# Mikrolysreklamen15.net
KiCad netlist of a schematic drawn in Altium Designer
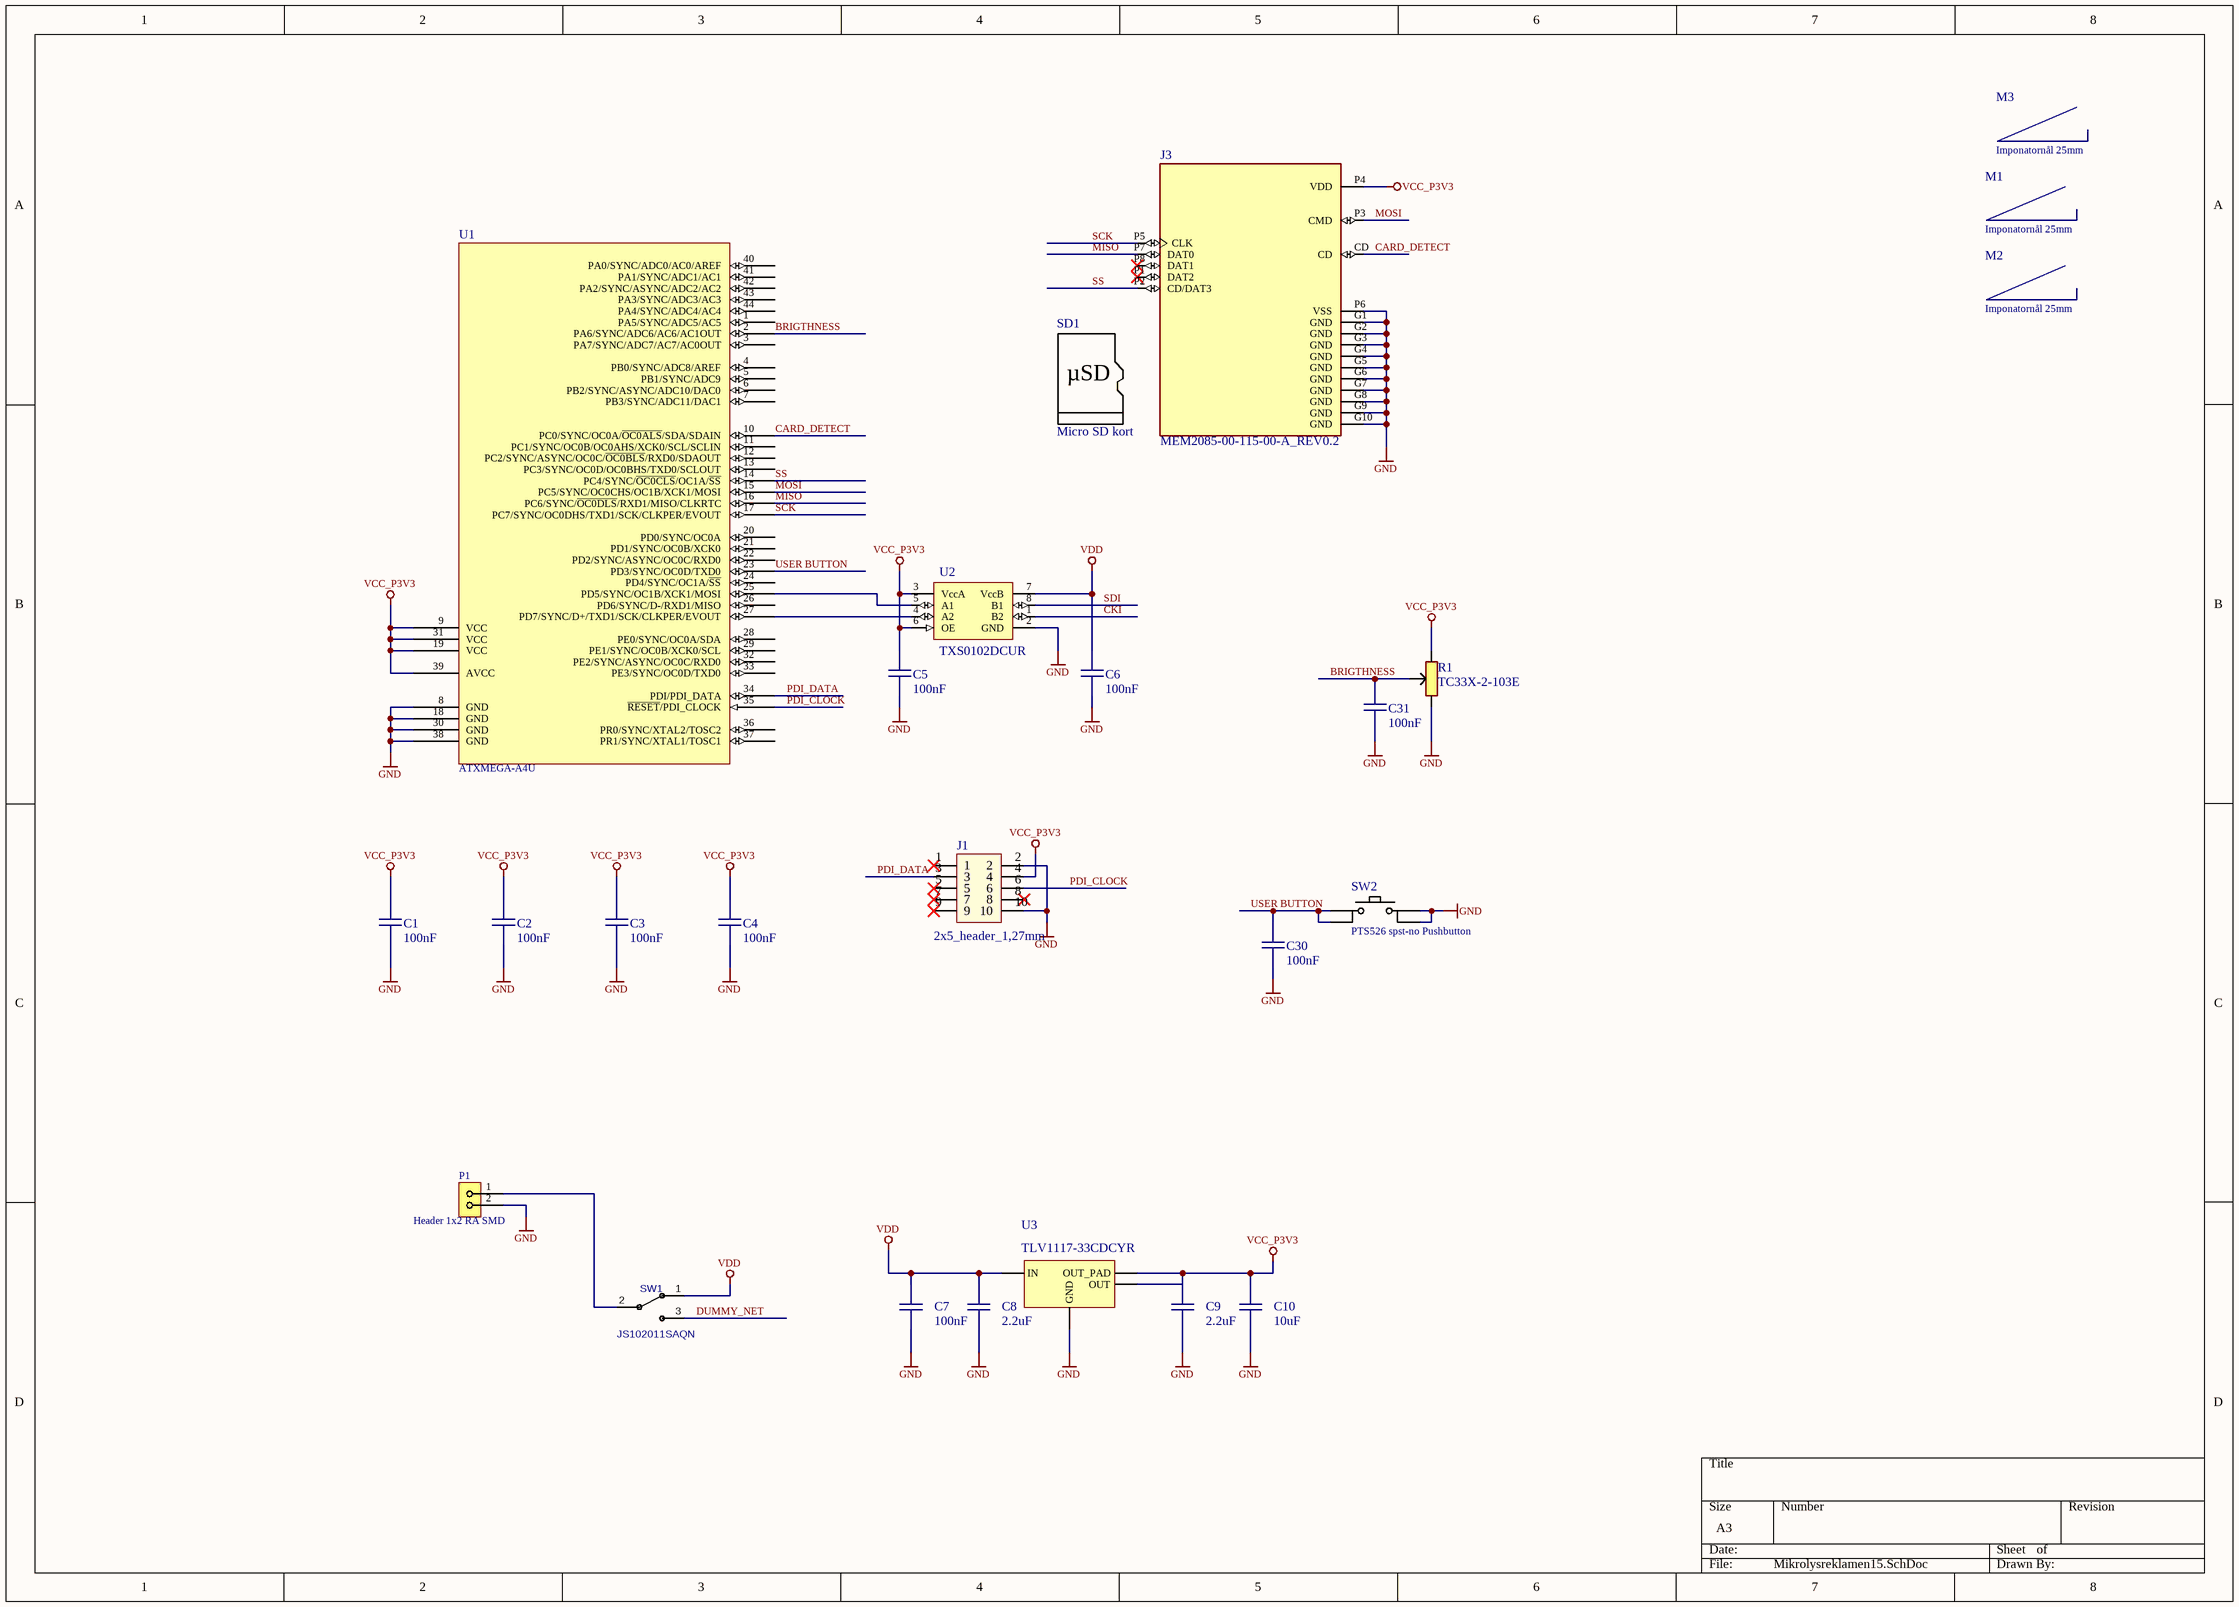
[diagram p0: Mikrolysreklamen15.SchDoc]

(export (version "E")
  (design (tool "Eeschema 10.0.6"))
  (components
    (comp (ref "C1")
      (value "100nF")
      (footprint "CAPC0603(1608)55_N")
      (libsource (lib "OVLib_64") (part "CAP"))
    )
    (comp (ref "C2")
      (value "100nF")
      (footprint "CAPC0603(1608)55_N")
      (libsource (lib "OVLib_64") (part "CAP"))
    )
    (comp (ref "C3")
      (value "100nF")
      (footprint "CAPC0603(1608)55_N")
      (libsource (lib "OVLib_64") (part "CAP"))
    )
    (comp (ref "C4")
      (value "100nF")
      (footprint "CAPC0603(1608)55_N")
      (libsource (lib "OVLib_64") (part "CAP"))
    )
    (comp (ref "C5")
      (value "100nF")
      (footprint "CAPC0603(1608)55_N")
      (libsource (lib "OVLib_64") (part "CAP"))
    )
    (comp (ref "C6")
      (value "100nF")
      (footprint "CAPC0603(1608)55_N")
      (libsource (lib "OVLib_64") (part "CAP"))
    )
    (comp (ref "C7")
      (value "100nF")
      (footprint "CAPC0603(1608)55_N")
      (libsource (lib "OVLib_64") (part "CAP"))
    )
    (comp (ref "C8")
      (value "2.2uF")
      (footprint "CAPC0603(1608)55_N")
      (libsource (lib "OVLib_64") (part "CAP"))
    )
    (comp (ref "C9")
      (value "2.2uF")
      (footprint "CAPC0603(1608)55_N")
      (libsource (lib "OVLib_64") (part "CAP"))
    )
    (comp (ref "C10")
      (value "10uF")
      (footprint "CAPC0805(2012)100_N")
      (libsource (lib "OVLib_64") (part "CAP"))
    )
    (comp (ref "C30")
      (value "100nF")
      (footprint "CAPC0603(1608)55_N")
      (libsource (lib "OVLib_64") (part "CAP"))
    )
    (comp (ref "C31")
      (value "100nF")
      (footprint "CAPC0603(1608)55_N")
      (libsource (lib "OVLib_64") (part "CAP"))
    )
    (comp (ref "J1")
      (value "2x5_header_1,27mm")
      (footprint "SMDHDRV10P127_2X5_615X330X560B")
      (libsource (lib "OVLib_64") (part "2x5_header_1,27mm"))
    )
    (comp (ref "J3")
      (value "MEM2085-00-115-00-A_REV0.2")
      (footprint "GCT_MEM2085-00-115-00-A_REV0.2")
      (description "MicroSD Push pull Memory Card Connector")
      (fields (field (name "MP") "MEM2085-00-115-00-A") (field (name "MF") "Global Connector Technology"))
      (libsource (lib "OVLib_64") (part "MEM2085-00-115-00-A_REV0.2"))
    )
    (comp (ref "M1")
      (value "Imponatornål 25mm")
      (footprint "Imponatornaal_liten")
      (description "nål til imponatorplate 25mm (Brooch back)")
      (libsource (lib "OVLib_64") (part "Imponatornaal"))
    )
    (comp (ref "M2")
      (value "Imponatornål 25mm")
      (footprint "Imponatornaal_liten")
      (description "nål til imponatorplate 25mm (Brooch back)")
      (libsource (lib "OVLib_64") (part "Imponatornaal"))
    )
    (comp (ref "M3")
      (value "Imponatornål 25mm")
      (footprint "Imponatornaal_liten")
      (description "nål til imponatorplate 25mm (Brooch back)")
      (libsource (lib "OVLib_64") (part "Imponatornaal"))
    )
    (comp (ref "P1") (value "Header 1x2 RA SMD") (libsource (lib "OVLib_64") (part "Header1x2")))
    (comp (ref "R1")
      (value "TC33X-2-103E")
      (footprint "TRIM_TC33X-2-103E")
      (libsource (lib "OVLib_64") (part "Potmeter"))
    )
    (comp (ref "SD1")
      (value "Micro SD kort")
      (footprint "microsdcard")
      (libsource (lib "OVLib_64") (part "microsdcard"))
    )
    (comp (ref "SW1") (value "JS102011SAQN") (libsource (lib "OVLib_64") (part "ToggleSwitch")))
    (comp (ref "SW2")
      (value "PTS526 spst-no Pushbutton")
      (footprint "PTS526_SK15_SMTR2_LFS")
      (libsource (lib "OVLib_64") (part "Pushbutton"))
    )
    (comp (ref "U1")
      (value "ATXMEGA-A4U")
      (footprint "TQFP80P1200X1200X120-44N")
      (libsource (lib "OVLib_64") (part "ATXMEGA-A4U"))
    )
    (comp (ref "U2") (value "TXS0102DCUR") (libsource (lib "OVLib_64") (part "TXS0102DCUR")))
    (comp (ref "U3")
      (value "TLV1117-33CDCYR")
      (footprint "SOT230P700X180-4N")
      (libsource (lib "OVLib_64") (part "LDO_REGULATOR"))
    )
  )
  (nets
    (net (code "1") (name "/BRIGTHNESS") (class "Default")
      (node (ref "C31") (pin "2") (pinfunction "2_2") (pintype "passive"))
      (node (ref "R1") (pin "2") (pinfunction "2_2") (pintype "passive"))
      (node (ref "U1") (pin "2") (pinfunction "PA6/SYNC/ADC6/AC6/AC1OUT_2") (pintype "bidirectional"))
    )
    (net (code "2") (name "/CARD_DETECT") (class "Default")
      (node (ref "J3") (pin "CD") (pinfunction "CD_CD") (pintype "bidirectional"))
      (node (ref "U1") (pin "10") (pinfunction "PC0/SYNC/OC0A/~{OC0ALS}/SDA/SDAIN_10") (pintype "bidirectional"))
    )
    (net (code "3") (name "/CKI") (class "Default")
      (node (ref "U2") (pin "1") (pinfunction "B2_1") (pintype "bidirectional"))
    )
    (net (code "4") (name "/DUMMY_NET") (class "Default")
      (node (ref "SW1") (pin "3") (pinfunction "3_3") (pintype "passive"))
    )
    (net (code "5") (name "/MISO") (class "Default")
      (node (ref "J3") (pin "P7") (pinfunction "DAT0_P7") (pintype "bidirectional"))
      (node (ref "U1") (pin "16") (pinfunction "PC6/SYNC/~{OC0DLS}/RXD1/MISO/CLKRTC_16") (pintype "bidirectional"))
    )
    (net (code "6") (name "/MOSI") (class "Default")
      (node (ref "J3") (pin "P3") (pinfunction "CMD_P3") (pintype "bidirectional"))
      (node (ref "U1") (pin "15") (pinfunction "PC5/SYNC/OC0CHS/OC1B/XCK1/MOSI_15") (pintype "bidirectional"))
    )
    (net (code "7") (name "/PDI_CLOCK") (class "Default")
      (node (ref "J1") (pin "6") (pinfunction "6_6") (pintype "power_in"))
      (node (ref "U1") (pin "35") (pinfunction "~{RESET}/PDI_CLOCK_35") (pintype "input"))
    )
    (net (code "8") (name "/PDI_DATA") (class "Default")
      (node (ref "J1") (pin "3") (pinfunction "3_3") (pintype "power_in"))
      (node (ref "U1") (pin "34") (pinfunction "PDI/PDI_DATA_34") (pintype "bidirectional"))
    )
    (net (code "9") (name "/SCK") (class "Default")
      (node (ref "J3") (pin "P5") (pinfunction "CLK_P5") (pintype "bidirectional"))
      (node (ref "U1") (pin "17") (pinfunction "PC7/SYNC/OC0DHS/TXD1/SCK/CLKPER/EVOUT_17") (pintype "bidirectional"))
    )
    (net (code "10") (name "/SDI") (class "Default")
      (node (ref "U2") (pin "8") (pinfunction "B1_8") (pintype "bidirectional"))
    )
    (net (code "11") (name "/SS") (class "Default")
      (node (ref "J3") (pin "P2") (pinfunction "CD/DAT3_P2") (pintype "bidirectional"))
      (node (ref "U1") (pin "14") (pinfunction "PC4/SYNC/~{OC0CLS}/OC1A/~{SS}_14") (pintype "bidirectional"))
    )
    (net (code "12") (name "/USER BUTTON") (class "Default")
      (node (ref "C30") (pin "2") (pinfunction "2_2") (pintype "passive"))
      (node (ref "SW2") (pin "1") (pinfunction "1_1") (pintype "passive"))
      (node (ref "SW2") (pin "2") (pinfunction "2_2") (pintype "passive"))
      (node (ref "U1") (pin "23") (pinfunction "PD3/SYNC/OC0D/TXD0_23") (pintype "bidirectional"))
    )
    (net (code "13") (name "GND") (class "Default")
      (node (ref "C1") (pin "1") (pinfunction "1_1") (pintype "passive"))
      (node (ref "C10") (pin "1") (pinfunction "1_1") (pintype "passive"))
      (node (ref "C2") (pin "1") (pinfunction "1_1") (pintype "passive"))
      (node (ref "C3") (pin "1") (pinfunction "1_1") (pintype "passive"))
      (node (ref "C30") (pin "1") (pinfunction "1_1") (pintype "passive"))
      (node (ref "C31") (pin "1") (pinfunction "1_1") (pintype "passive"))
      (node (ref "C4") (pin "1") (pinfunction "1_1") (pintype "passive"))
      (node (ref "C5") (pin "1") (pinfunction "1_1") (pintype "passive"))
      (node (ref "C6") (pin "1") (pinfunction "1_1") (pintype "passive"))
      (node (ref "C7") (pin "1") (pinfunction "1_1") (pintype "passive"))
      (node (ref "C8") (pin "1") (pinfunction "1_1") (pintype "passive"))
      (node (ref "C9") (pin "1") (pinfunction "1_1") (pintype "passive"))
      (node (ref "J1") (pin "10") (pinfunction "10_10") (pintype "power_in"))
      (node (ref "J1") (pin "2") (pinfunction "2_2") (pintype "power_in"))
      (node (ref "J3") (pin "G1") (pinfunction "GND_G1") (pintype "power_in"))
      (node (ref "J3") (pin "G10") (pinfunction "GND_G10") (pintype "power_in"))
      (node (ref "J3") (pin "G2") (pinfunction "GND_G2") (pintype "power_in"))
      (node (ref "J3") (pin "G3") (pinfunction "GND_G3") (pintype "power_in"))
      (node (ref "J3") (pin "G4") (pinfunction "GND_G4") (pintype "power_in"))
      (node (ref "J3") (pin "G5") (pinfunction "GND_G5") (pintype "power_in"))
      (node (ref "J3") (pin "G6") (pinfunction "GND_G6") (pintype "power_in"))
      (node (ref "J3") (pin "G7") (pinfunction "GND_G7") (pintype "power_in"))
      (node (ref "J3") (pin "G8") (pinfunction "GND_G8") (pintype "power_in"))
      (node (ref "J3") (pin "G9") (pinfunction "GND_G9") (pintype "power_in"))
      (node (ref "J3") (pin "P6") (pinfunction "VSS_P6") (pintype "power_in"))
      (node (ref "P1") (pin "2") (pinfunction "2_2") (pintype "passive"))
      (node (ref "R1") (pin "1") (pinfunction "1_1") (pintype "passive"))
      (node (ref "SW2") (pin "3") (pinfunction "3_3") (pintype "passive"))
      (node (ref "SW2") (pin "4") (pinfunction "4_4") (pintype "passive"))
      (node (ref "U1") (pin "18") (pinfunction "GND_18") (pintype "power_in"))
      (node (ref "U1") (pin "30") (pinfunction "GND_30") (pintype "power_in"))
      (node (ref "U1") (pin "38") (pinfunction "GND_38") (pintype "power_in"))
      (node (ref "U1") (pin "8") (pinfunction "GND_8") (pintype "power_in"))
      (node (ref "U2") (pin "2") (pinfunction "GND_2") (pintype "power_in"))
      (node (ref "U3") (pin "1") (pinfunction "GND_1") (pintype "power_in"))
    )
    (net (code "14") (name "Net-(P1-Pad1)") (class "Default")
      (node (ref "P1") (pin "1") (pinfunction "1_1") (pintype "passive"))
      (node (ref "SW1") (pin "2") (pinfunction "2_2") (pintype "passive"))
    )
    (net (code "15") (name "Net-(U1-PD5{slash}SYNC{slash}OC1B{slash}XCK1{slash}MOSI)") (class "Default")
      (node (ref "U1") (pin "25") (pinfunction "PD5/SYNC/OC1B/XCK1/MOSI_25") (pintype "bidirectional"))
      (node (ref "U2") (pin "5") (pinfunction "A1_5") (pintype "bidirectional"))
    )
    (net (code "16") (name "Net-(U1-PD7{slash}SYNC{slash}D+{slash}TXD1{slash}SCK{slash}CLKPER{slash}EVOUT)") (class "Default")
      (node (ref "U1") (pin "27") (pinfunction "PD7/SYNC/D+/TXD1/SCK/CLKPER/EVOUT_27") (pintype "bidirectional"))
      (node (ref "U2") (pin "4") (pinfunction "A2_4") (pintype "bidirectional"))
    )
    (net (code "17") (name "VCC_P3V3") (class "Default")
      (node (ref "C1") (pin "2") (pinfunction "2_2") (pintype "passive"))
      (node (ref "C10") (pin "2") (pinfunction "2_2") (pintype "passive"))
      (node (ref "C2") (pin "2") (pinfunction "2_2") (pintype "passive"))
      (node (ref "C3") (pin "2") (pinfunction "2_2") (pintype "passive"))
      (node (ref "C4") (pin "2") (pinfunction "2_2") (pintype "passive"))
      (node (ref "C5") (pin "2") (pinfunction "2_2") (pintype "passive"))
      (node (ref "C9") (pin "2") (pinfunction "2_2") (pintype "passive"))
      (node (ref "J1") (pin "4") (pinfunction "4_4") (pintype "power_in"))
      (node (ref "J3") (pin "P4") (pinfunction "VDD_P4") (pintype "power_in"))
      (node (ref "R1") (pin "3") (pinfunction "3_3") (pintype "passive"))
      (node (ref "U1") (pin "19") (pinfunction "VCC_19") (pintype "power_in"))
      (node (ref "U1") (pin "31") (pinfunction "VCC_31") (pintype "power_in"))
      (node (ref "U1") (pin "39") (pinfunction "AVCC_39") (pintype "power_in"))
      (node (ref "U1") (pin "9") (pinfunction "VCC_9") (pintype "power_in"))
      (node (ref "U2") (pin "3") (pinfunction "VccA_3") (pintype "power_in"))
      (node (ref "U2") (pin "6") (pinfunction "OE_6") (pintype "input"))
      (node (ref "U3") (pin "2") (pinfunction "OUT_PAD_2") (pintype "power_in"))
      (node (ref "U3") (pin "4") (pinfunction "OUT_4") (pintype "power_in"))
    )
    (net (code "18") (name "VDD") (class "Default")
      (node (ref "C6") (pin "2") (pinfunction "2_2") (pintype "passive"))
      (node (ref "C7") (pin "2") (pinfunction "2_2") (pintype "passive"))
      (node (ref "C8") (pin "2") (pinfunction "2_2") (pintype "passive"))
      (node (ref "SW1") (pin "1") (pinfunction "1_1") (pintype "passive"))
      (node (ref "U2") (pin "7") (pinfunction "VccB_7") (pintype "power_in"))
      (node (ref "U3") (pin "3") (pinfunction "IN_3") (pintype "power_in"))
    )
    (net (code "19") (name "unconnected-(J1-Pad1)") (class "Default")
      (node (ref "J1") (pin "1") (pinfunction "1_1") (pintype "power_in+no_connect"))
    )
    (net (code "20") (name "unconnected-(J1-Pad5)") (class "Default")
      (node (ref "J1") (pin "5") (pinfunction "5_5") (pintype "power_in+no_connect"))
    )
    (net (code "21") (name "unconnected-(J1-Pad7)") (class "Default")
      (node (ref "J1") (pin "7") (pinfunction "7_7") (pintype "power_in+no_connect"))
    )
    (net (code "22") (name "unconnected-(J1-Pad8)") (class "Default")
      (node (ref "J1") (pin "8") (pinfunction "8_8") (pintype "power_in+no_connect"))
    )
    (net (code "23") (name "unconnected-(J1-Pad9)") (class "Default")
      (node (ref "J1") (pin "9") (pinfunction "9_9") (pintype "power_in+no_connect"))
    )
    (net (code "24") (name "unconnected-(J3-DAT1-PadP8)") (class "Default")
      (node (ref "J3") (pin "P8") (pinfunction "DAT1_P8") (pintype "bidirectional+no_connect"))
    )
    (net (code "25") (name "unconnected-(J3-DAT2-PadP1)") (class "Default")
      (node (ref "J3") (pin "P1") (pinfunction "DAT2_P1") (pintype "bidirectional+no_connect"))
    )
    (net (code "26") (name "unconnected-(M1-Pad0)") (class "Default")
      (node (ref "M1") (pin "0") (pinfunction "0_0") (pintype "passive"))
    )
    (net (code "27") (name "unconnected-(M2-Pad0)") (class "Default")
      (node (ref "M2") (pin "0") (pinfunction "0_0") (pintype "passive"))
    )
    (net (code "28") (name "unconnected-(M3-Pad0)") (class "Default")
      (node (ref "M3") (pin "0") (pinfunction "0_0") (pintype "passive"))
    )
    (net (code "29") (name "unconnected-(U1-PA0{slash}SYNC{slash}ADC0{slash}AC0{slash}AREF-Pad40)") (class "Default")
      (node (ref "U1") (pin "40") (pinfunction "PA0/SYNC/ADC0/AC0/AREF_40") (pintype "bidirectional"))
    )
    (net (code "30") (name "unconnected-(U1-PA1{slash}SYNC{slash}ADC1{slash}AC1-Pad41)") (class "Default")
      (node (ref "U1") (pin "41") (pinfunction "PA1/SYNC/ADC1/AC1_41") (pintype "bidirectional"))
    )
    (net (code "31") (name "unconnected-(U1-PA2{slash}SYNC{slash}ASYNC{slash}ADC2{slash}AC2-Pad42)") (class "Default")
      (node (ref "U1") (pin "42") (pinfunction "PA2/SYNC/ASYNC/ADC2/AC2_42") (pintype "bidirectional"))
    )
    (net (code "32") (name "unconnected-(U1-PA3{slash}SYNC{slash}ADC3{slash}AC3-Pad43)") (class "Default")
      (node (ref "U1") (pin "43") (pinfunction "PA3/SYNC/ADC3/AC3_43") (pintype "bidirectional"))
    )
    (net (code "33") (name "unconnected-(U1-PA4{slash}SYNC{slash}ADC4{slash}AC4-Pad44)") (class "Default")
      (node (ref "U1") (pin "44") (pinfunction "PA4/SYNC/ADC4/AC4_44") (pintype "bidirectional"))
    )
    (net (code "34") (name "unconnected-(U1-PA5{slash}SYNC{slash}ADC5{slash}AC5-Pad1)") (class "Default")
      (node (ref "U1") (pin "1") (pinfunction "PA5/SYNC/ADC5/AC5_1") (pintype "bidirectional"))
    )
    (net (code "35") (name "unconnected-(U1-PA7{slash}SYNC{slash}ADC7{slash}AC7{slash}AC0OUT-Pad3)") (class "Default")
      (node (ref "U1") (pin "3") (pinfunction "PA7/SYNC/ADC7/AC7/AC0OUT_3") (pintype "bidirectional"))
    )
    (net (code "36") (name "unconnected-(U1-PB0{slash}SYNC{slash}ADC8{slash}AREF-Pad4)") (class "Default")
      (node (ref "U1") (pin "4") (pinfunction "PB0/SYNC/ADC8/AREF_4") (pintype "bidirectional"))
    )
    (net (code "37") (name "unconnected-(U1-PB1{slash}SYNC{slash}ADC9-Pad5)") (class "Default")
      (node (ref "U1") (pin "5") (pinfunction "PB1/SYNC/ADC9_5") (pintype "bidirectional"))
    )
    (net (code "38") (name "unconnected-(U1-PB2{slash}SYNC{slash}ASYNC{slash}ADC10{slash}DAC0-Pad6)") (class "Default")
      (node (ref "U1") (pin "6") (pinfunction "PB2/SYNC/ASYNC/ADC10/DAC0_6") (pintype "bidirectional"))
    )
    (net (code "39") (name "unconnected-(U1-PB3{slash}SYNC{slash}ADC11{slash}DAC1-Pad7)") (class "Default")
      (node (ref "U1") (pin "7") (pinfunction "PB3/SYNC/ADC11/DAC1_7") (pintype "bidirectional"))
    )
    (net (code "40") (name "unconnected-(U1-PC1{slash}SYNC{slash}OC0B{slash}OC0AHS{slash}XCK0{slash}SCL{slash}SCLIN-Pad11)") (class "Default")
      (node (ref "U1") (pin "11") (pinfunction "PC1/SYNC/OC0B/OC0AHS/XCK0/SCL/SCLIN_11") (pintype "bidirectional"))
    )
    (net (code "41") (name "unconnected-(U1-PC2{slash}SYNC{slash}ASYNC{slash}OC0C{slash}~{OC0BLS}{slash}RXD0{slash}SDAOUT-Pad12)") (class "Default")
      (node (ref "U1") (pin "12") (pinfunction "PC2/SYNC/ASYNC/OC0C/~{OC0BLS}/RXD0/SDAOUT_12") (pintype "bidirectional"))
    )
    (net (code "42") (name "unconnected-(U1-PC3{slash}SYNC{slash}OC0D{slash}OC0BHS{slash}TXD0{slash}SCLOUT-Pad13)") (class "Default")
      (node (ref "U1") (pin "13") (pinfunction "PC3/SYNC/OC0D/OC0BHS/TXD0/SCLOUT_13") (pintype "bidirectional"))
    )
    (net (code "43") (name "unconnected-(U1-PD0{slash}SYNC{slash}OC0A-Pad20)") (class "Default")
      (node (ref "U1") (pin "20") (pinfunction "PD0/SYNC/OC0A_20") (pintype "bidirectional"))
    )
    (net (code "44") (name "unconnected-(U1-PD1{slash}SYNC{slash}OC0B{slash}XCK0-Pad21)") (class "Default")
      (node (ref "U1") (pin "21") (pinfunction "PD1/SYNC/OC0B/XCK0_21") (pintype "bidirectional"))
    )
    (net (code "45") (name "unconnected-(U1-PD2{slash}SYNC{slash}ASYNC{slash}OC0C{slash}RXD0-Pad22)") (class "Default")
      (node (ref "U1") (pin "22") (pinfunction "PD2/SYNC/ASYNC/OC0C/RXD0_22") (pintype "bidirectional"))
    )
    (net (code "46") (name "unconnected-(U1-PD4{slash}SYNC{slash}OC1A{slash}~{SS}-Pad24)") (class "Default")
      (node (ref "U1") (pin "24") (pinfunction "PD4/SYNC/OC1A/~{SS}_24") (pintype "bidirectional"))
    )
    (net (code "47") (name "unconnected-(U1-PD6{slash}SYNC{slash}D-{slash}RXD1{slash}MISO-Pad26)") (class "Default")
      (node (ref "U1") (pin "26") (pinfunction "PD6/SYNC/D-/RXD1/MISO_26") (pintype "bidirectional"))
    )
    (net (code "48") (name "unconnected-(U1-PE0{slash}SYNC{slash}OC0A{slash}SDA-Pad28)") (class "Default")
      (node (ref "U1") (pin "28") (pinfunction "PE0/SYNC/OC0A/SDA_28") (pintype "bidirectional"))
    )
    (net (code "49") (name "unconnected-(U1-PE1{slash}SYNC{slash}OC0B{slash}XCK0{slash}SCL-Pad29)") (class "Default")
      (node (ref "U1") (pin "29") (pinfunction "PE1/SYNC/OC0B/XCK0/SCL_29") (pintype "bidirectional"))
    )
    (net (code "50") (name "unconnected-(U1-PE2{slash}SYNC{slash}ASYNC{slash}OC0C{slash}RXD0-Pad32)") (class "Default")
      (node (ref "U1") (pin "32") (pinfunction "PE2/SYNC/ASYNC/OC0C/RXD0_32") (pintype "bidirectional"))
    )
    (net (code "51") (name "unconnected-(U1-PE3{slash}SYNC{slash}OC0D{slash}TXD0-Pad33)") (class "Default")
      (node (ref "U1") (pin "33") (pinfunction "PE3/SYNC/OC0D/TXD0_33") (pintype "bidirectional"))
    )
    (net (code "52") (name "unconnected-(U1-PR0{slash}SYNC{slash}XTAL2{slash}TOSC2-Pad36)") (class "Default")
      (node (ref "U1") (pin "36") (pinfunction "PR0/SYNC/XTAL2/TOSC2_36") (pintype "bidirectional"))
    )
    (net (code "53") (name "unconnected-(U1-PR1{slash}SYNC{slash}XTAL1{slash}TOSC1-Pad37)") (class "Default")
      (node (ref "U1") (pin "37") (pinfunction "PR1/SYNC/XTAL1/TOSC1_37") (pintype "bidirectional"))
    )
  )
)
